# 01_giris.net
KiCad netlist of a schematic drawn in EAGLE
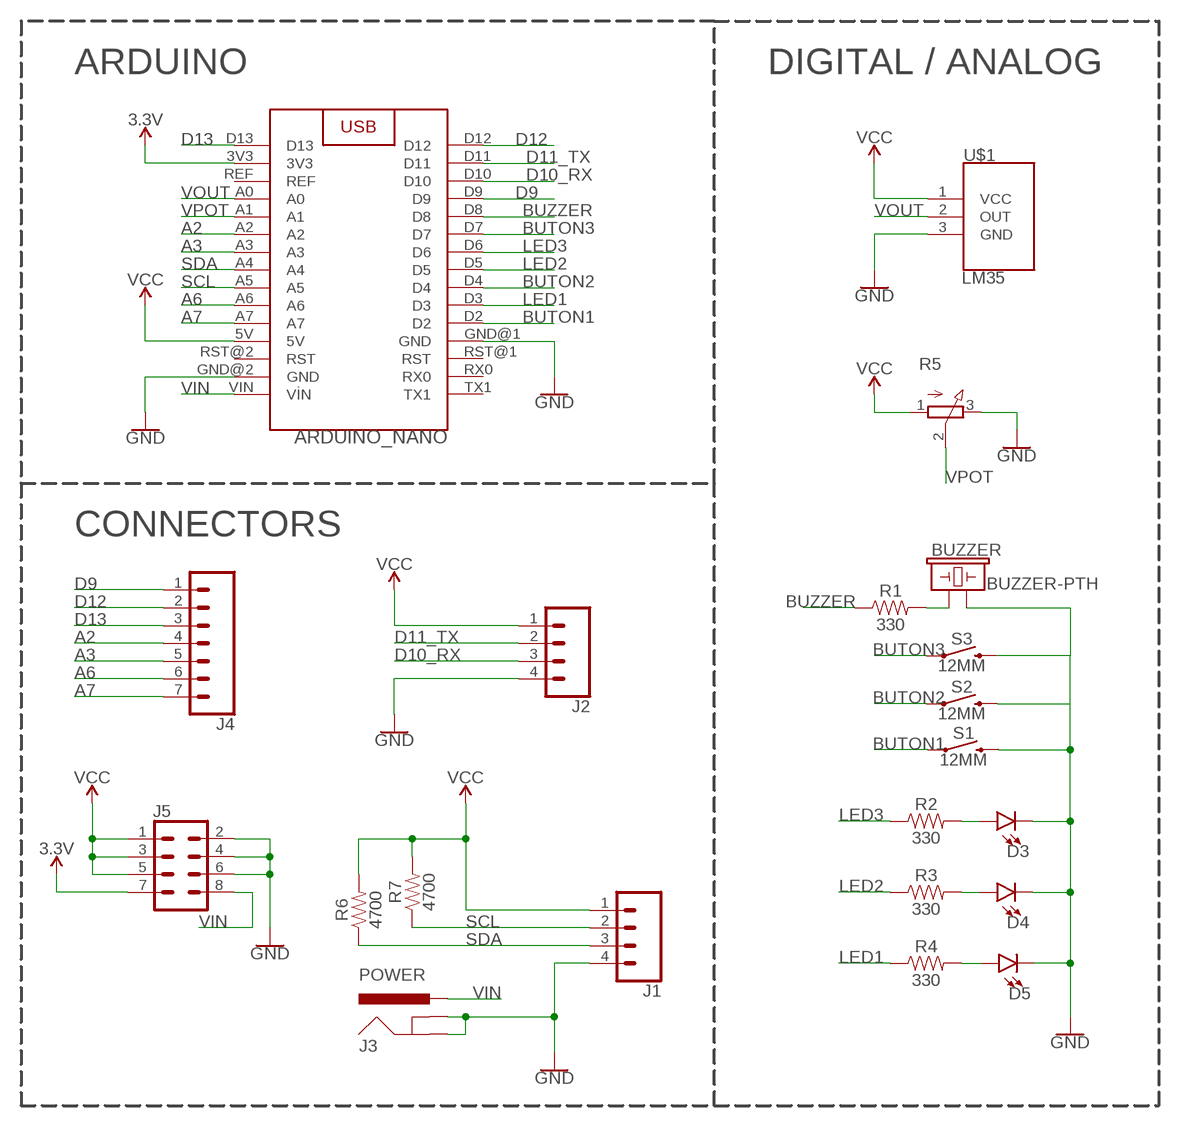
[diagram p0: schematic, sheet 1]

(export (version "E")
  (design (tool "Eeschema 10.0.6"))
  (components
    (comp (ref "ARDUINO_NANO")
      (value "ARDUINO_NANO")
      (footprint "eagle-import:ARDUINO_NANO")
      (libsource (lib "eagle-import") (part "ARDUINO_NANO"))
    )
    (comp (ref "BUZZER")
      (value "BUZZER-PTH")
      (footprint "eagle-import:BUZZER-12MM")
      (libsource (lib "eagle-import") (part "BUZZER-PTH"))
    )
    (comp (ref "D3")
      (value "LED-3MM-NO_SILK")
      (footprint "eagle-import:LED_3MM-NS")
      (libsource (lib "eagle-import") (part "LED-3MM-NO_SILK"))
    )
    (comp (ref "D4")
      (value "LED-3MM-NO_SILK")
      (footprint "eagle-import:LED_3MM-NS")
      (libsource (lib "eagle-import") (part "LED-3MM-NO_SILK"))
    )
    (comp (ref "D5")
      (value "LED-3MM-NO_SILK")
      (footprint "eagle-import:LED_3MM-NS")
      (libsource (lib "eagle-import") (part "LED-3MM-NO_SILK"))
    )
    (comp (ref "J1")
      (value "CONN_04")
      (footprint "eagle-import:1X04")
      (libsource (lib "eagle-import") (part "CONN_04"))
    )
    (comp (ref "J2")
      (value "CONN_04")
      (footprint "eagle-import:1X04")
      (libsource (lib "eagle-import") (part "CONN_04"))
    )
    (comp (ref "J3")
      (value "POWER")
      (footprint "eagle-import:POWER_JACK_PTH")
      (libsource (lib "eagle-import") (part "POWER_JACK"))
    )
    (comp (ref "J4")
      (value "CONN_07")
      (footprint "eagle-import:1X07")
      (libsource (lib "eagle-import") (part "CONN_07"))
    )
    (comp (ref "J5")
      (value "CONN_04X2")
      (footprint "eagle-import:2X4")
      (libsource (lib "eagle-import") (part "CONN_04X2"))
    )
    (comp (ref "R1")
      (value "330")
      (footprint "eagle-import:AXIAL-0.3")
      (libsource (lib "eagle-import") (part "1KOHM-HORIZ-1/4W-5%"))
    )
    (comp (ref "R2")
      (value "330")
      (footprint "eagle-import:AXIAL-0.3")
      (libsource (lib "eagle-import") (part "1KOHM-HORIZ-1/4W-5%"))
    )
    (comp (ref "R3")
      (value "330")
      (footprint "eagle-import:AXIAL-0.3")
      (libsource (lib "eagle-import") (part "1KOHM-HORIZ-1/4W-5%"))
    )
    (comp (ref "R4")
      (value "330")
      (footprint "eagle-import:AXIAL-0.3")
      (libsource (lib "eagle-import") (part "1KOHM-HORIZ-1/4W-5%"))
    )
    (comp (ref "R5")
      (value "3RP/1610N")
      (footprint "eagle-import:3RP_1610N")
      (libsource (lib "eagle-import") (part "3RP/1610N"))
    )
    (comp (ref "R6")
      (value "4700")
      (footprint "eagle-import:AXIAL-0.3")
      (libsource (lib "eagle-import") (part "1KOHM-HORIZ-1/4W-5%"))
    )
    (comp (ref "R7")
      (value "4700")
      (footprint "eagle-import:AXIAL-0.3")
      (libsource (lib "eagle-import") (part "1KOHM-HORIZ-1/4W-5%"))
    )
    (comp (ref "S1")
      (value "12MM")
      (footprint "eagle-import:TACTILE_SWITCH_PTH_12MM")
      (libsource (lib "eagle-import") (part "MOMENTARY-SWITCH-SPST-PTH-12MM"))
    )
    (comp (ref "S2")
      (value "12MM")
      (footprint "eagle-import:TACTILE_SWITCH_PTH_12MM")
      (libsource (lib "eagle-import") (part "MOMENTARY-SWITCH-SPST-PTH-12MM"))
    )
    (comp (ref "S3")
      (value "12MM")
      (footprint "eagle-import:TACTILE_SWITCH_PTH_12MM")
      (libsource (lib "eagle-import") (part "MOMENTARY-SWITCH-SPST-PTH-12MM"))
    )
    (comp (ref "U$1")
      (value "LM35")
      (footprint "eagle-import:TO-92")
      (libsource (lib "eagle-import") (part "LM35"))
    )
  )
  (nets
    (net (code "1") (name "/A2") (class "Default")
      (node (ref "ARDUINO_NANO") (pin "A2") (pinfunction "A2_A2") (pintype "bidirectional"))
      (node (ref "J4") (pin "4") (pinfunction "4_4") (pintype "passive"))
    )
    (net (code "2") (name "/A3") (class "Default")
      (node (ref "ARDUINO_NANO") (pin "A3") (pinfunction "A3_A3") (pintype "bidirectional"))
      (node (ref "J4") (pin "5") (pinfunction "5_5") (pintype "passive"))
    )
    (net (code "3") (name "/A6") (class "Default")
      (node (ref "ARDUINO_NANO") (pin "A6") (pinfunction "A6_A6") (pintype "bidirectional"))
      (node (ref "J4") (pin "6") (pinfunction "6_6") (pintype "passive"))
    )
    (net (code "4") (name "/A7") (class "Default")
      (node (ref "ARDUINO_NANO") (pin "A7") (pinfunction "A7_A7") (pintype "bidirectional"))
      (node (ref "J4") (pin "7") (pinfunction "7_7") (pintype "passive"))
    )
    (net (code "5") (name "/BUTON1") (class "Default")
      (node (ref "ARDUINO_NANO") (pin "D2") (pinfunction "D2_D2") (pintype "bidirectional"))
      (node (ref "S1") (pin "1") (pinfunction "1_1") (pintype "passive"))
    )
    (net (code "6") (name "/BUTON2") (class "Default")
      (node (ref "ARDUINO_NANO") (pin "D4") (pinfunction "D4_D4") (pintype "bidirectional"))
      (node (ref "S2") (pin "1") (pinfunction "1_1") (pintype "passive"))
    )
    (net (code "7") (name "/BUTON3") (class "Default")
      (node (ref "ARDUINO_NANO") (pin "D7") (pinfunction "D7_D7") (pintype "bidirectional"))
      (node (ref "S3") (pin "1") (pinfunction "1_1") (pintype "passive"))
    )
    (net (code "8") (name "/BUZZER") (class "Default")
      (node (ref "ARDUINO_NANO") (pin "D8") (pinfunction "D8_D8") (pintype "bidirectional"))
      (node (ref "R1") (pin "P$1") (pinfunction "1_P$1") (pintype "passive"))
    )
    (net (code "9") (name "/D9") (class "Default")
      (node (ref "ARDUINO_NANO") (pin "D9") (pinfunction "D9_D9") (pintype "bidirectional"))
      (node (ref "J4") (pin "1") (pinfunction "1_1") (pintype "passive"))
    )
    (net (code "10") (name "/D10_RX") (class "Default")
      (node (ref "ARDUINO_NANO") (pin "D10") (pinfunction "D10_D10") (pintype "bidirectional"))
      (node (ref "J2") (pin "3") (pinfunction "3_3") (pintype "passive"))
    )
    (net (code "11") (name "/D11_TX") (class "Default")
      (node (ref "ARDUINO_NANO") (pin "D11") (pinfunction "D11_D11") (pintype "bidirectional"))
      (node (ref "J2") (pin "2") (pinfunction "2_2") (pintype "passive"))
    )
    (net (code "12") (name "/D12") (class "Default")
      (node (ref "ARDUINO_NANO") (pin "D12") (pinfunction "D12_D12") (pintype "bidirectional"))
      (node (ref "J4") (pin "2") (pinfunction "2_2") (pintype "passive"))
    )
    (net (code "13") (name "/D13") (class "Default")
      (node (ref "ARDUINO_NANO") (pin "D13") (pinfunction "D13_D13") (pintype "bidirectional"))
      (node (ref "J4") (pin "3") (pinfunction "3_3") (pintype "passive"))
    )
    (net (code "14") (name "/LED1") (class "Default")
      (node (ref "ARDUINO_NANO") (pin "D3") (pinfunction "D3_D3") (pintype "bidirectional"))
      (node (ref "R4") (pin "P$1") (pinfunction "1_P$1") (pintype "passive"))
    )
    (net (code "15") (name "/LED2") (class "Default")
      (node (ref "ARDUINO_NANO") (pin "D5") (pinfunction "D5_D5") (pintype "bidirectional"))
      (node (ref "R3") (pin "P$1") (pinfunction "1_P$1") (pintype "passive"))
    )
    (net (code "16") (name "/LED3") (class "Default")
      (node (ref "ARDUINO_NANO") (pin "D6") (pinfunction "D6_D6") (pintype "bidirectional"))
      (node (ref "R2") (pin "P$1") (pinfunction "1_P$1") (pintype "passive"))
    )
    (net (code "17") (name "/SCL") (class "Default")
      (node (ref "ARDUINO_NANO") (pin "A5") (pinfunction "A5_A5") (pintype "bidirectional"))
      (node (ref "J1") (pin "2") (pinfunction "2_2") (pintype "passive"))
      (node (ref "R7") (pin "P$1") (pinfunction "1_P$1") (pintype "passive"))
    )
    (net (code "18") (name "/SDA") (class "Default")
      (node (ref "ARDUINO_NANO") (pin "A4") (pinfunction "A4_A4") (pintype "bidirectional"))
      (node (ref "J1") (pin "3") (pinfunction "3_3") (pintype "passive"))
      (node (ref "R6") (pin "P$1") (pinfunction "1_P$1") (pintype "passive"))
    )
    (net (code "19") (name "/VIN") (class "Default")
      (node (ref "ARDUINO_NANO") (pin "VIN") (pinfunction "VİN_VIN") (pintype "bidirectional"))
      (node (ref "J3") (pin "PWR") (pinfunction "PWR_PWR") (pintype "bidirectional"))
      (node (ref "J5") (pin "8") (pinfunction "8_8") (pintype "passive"))
    )
    (net (code "20") (name "/VOUT") (class "Default")
      (node (ref "ARDUINO_NANO") (pin "A0") (pinfunction "A0_A0") (pintype "bidirectional"))
      (node (ref "U$1") (pin "2") (pinfunction "OUT_2") (pintype "bidirectional"))
    )
    (net (code "21") (name "/VPOT") (class "Default")
      (node (ref "ARDUINO_NANO") (pin "A1") (pinfunction "A1_A1") (pintype "bidirectional"))
      (node (ref "R5") (pin "2") (pinfunction "S_2") (pintype "passive"))
    )
    (net (code "22") (name "3.3V") (class "Default")
      (node (ref "ARDUINO_NANO") (pin "3V3") (pinfunction "3V3_3V3") (pintype "bidirectional"))
      (node (ref "J5") (pin "7") (pinfunction "7_7") (pintype "passive"))
    )
    (net (code "23") (name "GND") (class "Default")
      (node (ref "ARDUINO_NANO") (pin "GND@1") (pinfunction "GND_GND@1") (pintype "bidirectional"))
      (node (ref "ARDUINO_NANO") (pin "GND@2") (pinfunction "GND_GND@2") (pintype "bidirectional"))
      (node (ref "BUZZER") (pin "-") (pinfunction "2_-") (pintype "passive"))
      (node (ref "D3") (pin "K") (pinfunction "C_K") (pintype "passive"))
      (node (ref "D4") (pin "K") (pinfunction "C_K") (pintype "passive"))
      (node (ref "D5") (pin "K") (pinfunction "C_K") (pintype "passive"))
      (node (ref "J1") (pin "4") (pinfunction "4_4") (pintype "passive"))
      (node (ref "J2") (pin "4") (pinfunction "4_4") (pintype "passive"))
      (node (ref "J3") (pin "GND") (pinfunction "GND_GND") (pintype "bidirectional"))
      (node (ref "J3") (pin "GNDBREAK") (pinfunction "GNDBREAK_GNDBREAK") (pintype "bidirectional"))
      (node (ref "J5") (pin "2") (pinfunction "2_2") (pintype "passive"))
      (node (ref "J5") (pin "4") (pinfunction "4_4") (pintype "passive"))
      (node (ref "J5") (pin "6") (pinfunction "6_6") (pintype "passive"))
      (node (ref "R5") (pin "3") (pinfunction "E_3") (pintype "passive"))
      (node (ref "S1") (pin "3") (pinfunction "2_3") (pintype "passive"))
      (node (ref "S2") (pin "3") (pinfunction "2_3") (pintype "passive"))
      (node (ref "S3") (pin "3") (pinfunction "2_3") (pintype "passive"))
      (node (ref "U$1") (pin "3") (pinfunction "GND_3") (pintype "bidirectional"))
    )
    (net (code "24") (name "Net-(BUZZER-1)") (class "Default")
      (node (ref "BUZZER") (pin "+") (pinfunction "1_+") (pintype "passive"))
      (node (ref "R1") (pin "P$2") (pinfunction "2_P$2") (pintype "passive"))
    )
    (net (code "25") (name "Net-(R2-2)") (class "Default")
      (node (ref "D3") (pin "A") (pinfunction "A_A") (pintype "passive"))
      (node (ref "R2") (pin "P$2") (pinfunction "2_P$2") (pintype "passive"))
    )
    (net (code "26") (name "Net-(R3-2)") (class "Default")
      (node (ref "D4") (pin "A") (pinfunction "A_A") (pintype "passive"))
      (node (ref "R3") (pin "P$2") (pinfunction "2_P$2") (pintype "passive"))
    )
    (net (code "27") (name "Net-(R4-2)") (class "Default")
      (node (ref "D5") (pin "A") (pinfunction "A_A") (pintype "passive"))
      (node (ref "R4") (pin "P$2") (pinfunction "2_P$2") (pintype "passive"))
    )
    (net (code "28") (name "VCC") (class "Default")
      (node (ref "ARDUINO_NANO") (pin "5V") (pinfunction "5V_5V") (pintype "bidirectional"))
      (node (ref "J1") (pin "1") (pinfunction "1_1") (pintype "passive"))
      (node (ref "J2") (pin "1") (pinfunction "1_1") (pintype "passive"))
      (node (ref "J5") (pin "1") (pinfunction "1_1") (pintype "passive"))
      (node (ref "J5") (pin "3") (pinfunction "3_3") (pintype "passive"))
      (node (ref "J5") (pin "5") (pinfunction "5_5") (pintype "passive"))
      (node (ref "R5") (pin "1") (pinfunction "A_1") (pintype "passive"))
      (node (ref "R6") (pin "P$2") (pinfunction "2_P$2") (pintype "passive"))
      (node (ref "R7") (pin "P$2") (pinfunction "2_P$2") (pintype "passive"))
      (node (ref "U$1") (pin "1") (pinfunction "VCC_1") (pintype "bidirectional"))
    )
    (net (code "29") (name "unconnected-(ARDUINO_NANO-PadREF)") (class "Default")
      (node (ref "ARDUINO_NANO") (pin "REF") (pinfunction "REF_REF") (pintype "bidirectional"))
    )
    (net (code "30") (name "unconnected-(ARDUINO_NANO-PadRX0)") (class "Default")
      (node (ref "ARDUINO_NANO") (pin "RX0") (pinfunction "RX0_RX0") (pintype "bidirectional"))
    )
    (net (code "31") (name "unconnected-(ARDUINO_NANO-PadTX1)") (class "Default")
      (node (ref "ARDUINO_NANO") (pin "TX1") (pinfunction "TX1_TX1") (pintype "bidirectional"))
    )
    (net (code "32") (name "unconnected-(ARDUINO_NANO-RST-PadRST@1)") (class "Default")
      (node (ref "ARDUINO_NANO") (pin "RST@1") (pinfunction "RST_RST@1") (pintype "bidirectional"))
    )
    (net (code "33") (name "unconnected-(ARDUINO_NANO-RST-PadRST@2)") (class "Default")
      (node (ref "ARDUINO_NANO") (pin "RST@2") (pinfunction "RST_RST@2") (pintype "bidirectional"))
    )
  )
)
